# strobeAT10_Lite.net
KiCad netlist of a schematic drawn in EAGLE
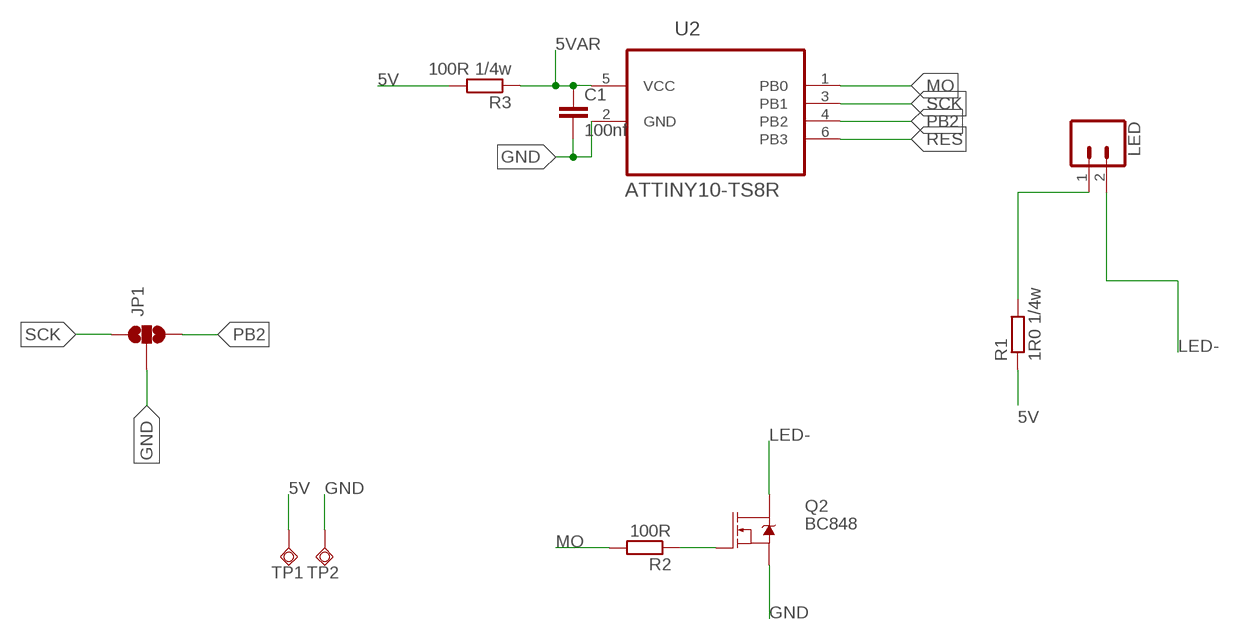
[diagram p0: schematic, sheet 1]

(export (version "E")
  (design (tool "Eeschema 10.0.6"))
  (components
    (comp (ref "C1")
      (value "100nf")
      (footprint "eagle-import:C0603")
      (libsource (lib "eagle-import") (part "C-EUC0603"))
    )
    (comp (ref "JP1")
      (value "JUMPER-SMT_3_NO_SILK")
      (footprint "eagle-import:SMT-JUMPER_3_NO_SILK")
      (libsource (lib "eagle-import") (part "JUMPER-SMT_3_NO_SILK"))
    )
    (comp (ref "LED")
      (value "CONN_02PTH3")
      (footprint "eagle-import:1X02_LONGPADS")
      (libsource (lib "eagle-import") (part "CONN_02PTH3"))
    )
    (comp (ref "Q2")
      (value "BC848")
      (footprint "eagle-import:SOT23-3")
      (libsource (lib "eagle-import") (part "MOSFET-NCH-AO3404A"))
    )
    (comp (ref "R1")
      (value "1R0 1/4w")
      (footprint "eagle-import:R0805")
      (libsource (lib "eagle-import") (part "R-EU_R0805"))
    )
    (comp (ref "R2")
      (value "100R")
      (footprint "eagle-import:R0603")
      (libsource (lib "eagle-import") (part "R-EU_R0603"))
    )
    (comp (ref "R3")
      (value "100R 1/4w")
      (footprint "eagle-import:R0805")
      (libsource (lib "eagle-import") (part "R-EU_R0805"))
    )
    (comp (ref "TP1")
      (value "TPSQPAD1-13Y")
      (footprint "eagle-import:P1-13Y")
      (libsource (lib "eagle-import") (part "TPSQPAD1-13Y"))
    )
    (comp (ref "TP2")
      (value "TPSQPAD1-13Y")
      (footprint "eagle-import:P1-13Y")
      (libsource (lib "eagle-import") (part "TPSQPAD1-13Y"))
    )
    (comp (ref "U2")
      (value "ATTINY10-TS8R")
      (footprint "eagle-import:SOT95P280X145-6N")
      (fields (field (name "MF") "Microchip"))
      (libsource (lib "eagle-import") (part "ATTINY10-TS8R"))
    )
  )
  (nets
    (net (code "1") (name "/5V") (class "Default")
      (node (ref "R1") (pin "1") (pinfunction "1_1") (pintype "passive"))
      (node (ref "R3") (pin "2") (pinfunction "2_2") (pintype "passive"))
      (node (ref "TP1") (pin "TP") (pinfunction "TP_TP") (pintype "input"))
    )
    (net (code "2") (name "/5VAR") (class "Default")
      (node (ref "C1") (pin "1") (pinfunction "1_1") (pintype "passive"))
      (node (ref "R3") (pin "1") (pinfunction "1_1") (pintype "passive"))
      (node (ref "U2") (pin "5") (pinfunction "VCC_5") (pintype "power_in"))
    )
    (net (code "3") (name "/LED-") (class "Default")
      (node (ref "LED") (pin "2") (pinfunction "2_2") (pintype "passive"))
      (node (ref "Q2") (pin "3") (pinfunction "D_3") (pintype "bidirectional"))
    )
    (net (code "4") (name "GND") (class "Default")
      (node (ref "C1") (pin "2") (pinfunction "2_2") (pintype "passive"))
      (node (ref "JP1") (pin "2") (pinfunction "2_2") (pintype "passive"))
      (node (ref "Q2") (pin "2") (pinfunction "S_2") (pintype "bidirectional"))
      (node (ref "TP2") (pin "TP") (pinfunction "TP_TP") (pintype "input"))
      (node (ref "U2") (pin "2") (pinfunction "GND_2") (pintype "passive"))
    )
    (net (code "5") (name "MO") (class "Default")
      (node (ref "R2") (pin "2") (pinfunction "2_2") (pintype "passive"))
      (node (ref "U2") (pin "1") (pinfunction "PB0_1") (pintype "bidirectional"))
    )
    (net (code "6") (name "Net-(LED-Pad1)") (class "Default")
      (node (ref "LED") (pin "1") (pinfunction "1_1") (pintype "passive"))
      (node (ref "R1") (pin "2") (pinfunction "2_2") (pintype "passive"))
    )
    (net (code "7") (name "Net-(Q2-G)") (class "Default")
      (node (ref "Q2") (pin "1") (pinfunction "G_1") (pintype "bidirectional"))
      (node (ref "R2") (pin "1") (pinfunction "1_1") (pintype "passive"))
    )
    (net (code "8") (name "PB2") (class "Default")
      (node (ref "JP1") (pin "3") (pinfunction "3_3") (pintype "passive"))
      (node (ref "U2") (pin "4") (pinfunction "PB2_4") (pintype "bidirectional"))
    )
    (net (code "9") (name "RES") (class "Default")
      (node (ref "U2") (pin "6") (pinfunction "PB3_6") (pintype "bidirectional"))
    )
    (net (code "10") (name "SCK") (class "Default")
      (node (ref "JP1") (pin "1") (pinfunction "1_1") (pintype "passive"))
      (node (ref "U2") (pin "3") (pinfunction "PB1_3") (pintype "bidirectional"))
    )
  )
)
